# rain-drop-voltage-divider-v1_1.net
KiCad netlist of a schematic drawn in EAGLE
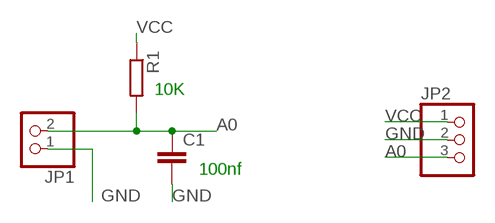
[diagram p0: schematic, sheet 1]

(export (version "E")
  (design (tool "Eeschema 10.0.6"))
  (components
    (comp (ref "C1")
      (value "C2.5/2")
      (footprint "eagle-import:C2.5-2")
      (libsource (lib "eagle-import") (part "C2.5/2"))
    )
    (comp (ref "JP1")
      (value "PINHD-1X2")
      (footprint "eagle-import:1X02")
      (libsource (lib "eagle-import") (part "PINHD-1X2"))
    )
    (comp (ref "JP2")
      (value "PINHD-1X3")
      (footprint "eagle-import:1X03")
      (libsource (lib "eagle-import") (part "PINHD-1X3"))
    )
    (comp (ref "R1")
      (value "R-EU_0204/7")
      (footprint "eagle-import:0204_7")
      (libsource (lib "eagle-import") (part "R-EU_0204/7"))
    )
  )
  (nets
    (net (code "1") (name "/A0") (class "Default")
      (node (ref "C1") (pin "1") (pinfunction "1_1") (pintype "passive"))
      (node (ref "JP1") (pin "2") (pinfunction "2_2") (pintype "passive"))
      (node (ref "JP2") (pin "3") (pinfunction "3_3") (pintype "passive"))
      (node (ref "R1") (pin "2") (pinfunction "2_2") (pintype "passive"))
    )
    (net (code "2") (name "/GND") (class "Default")
      (node (ref "C1") (pin "2") (pinfunction "2_2") (pintype "passive"))
      (node (ref "JP1") (pin "1") (pinfunction "1_1") (pintype "passive"))
      (node (ref "JP2") (pin "2") (pinfunction "2_2") (pintype "passive"))
    )
    (net (code "3") (name "/VCC") (class "Default")
      (node (ref "JP2") (pin "1") (pinfunction "1_1") (pintype "passive"))
      (node (ref "R1") (pin "1") (pinfunction "1_1") (pintype "passive"))
    )
  )
)
